# Sheet1.net
KiCad netlist of a schematic drawn in Altium Designer
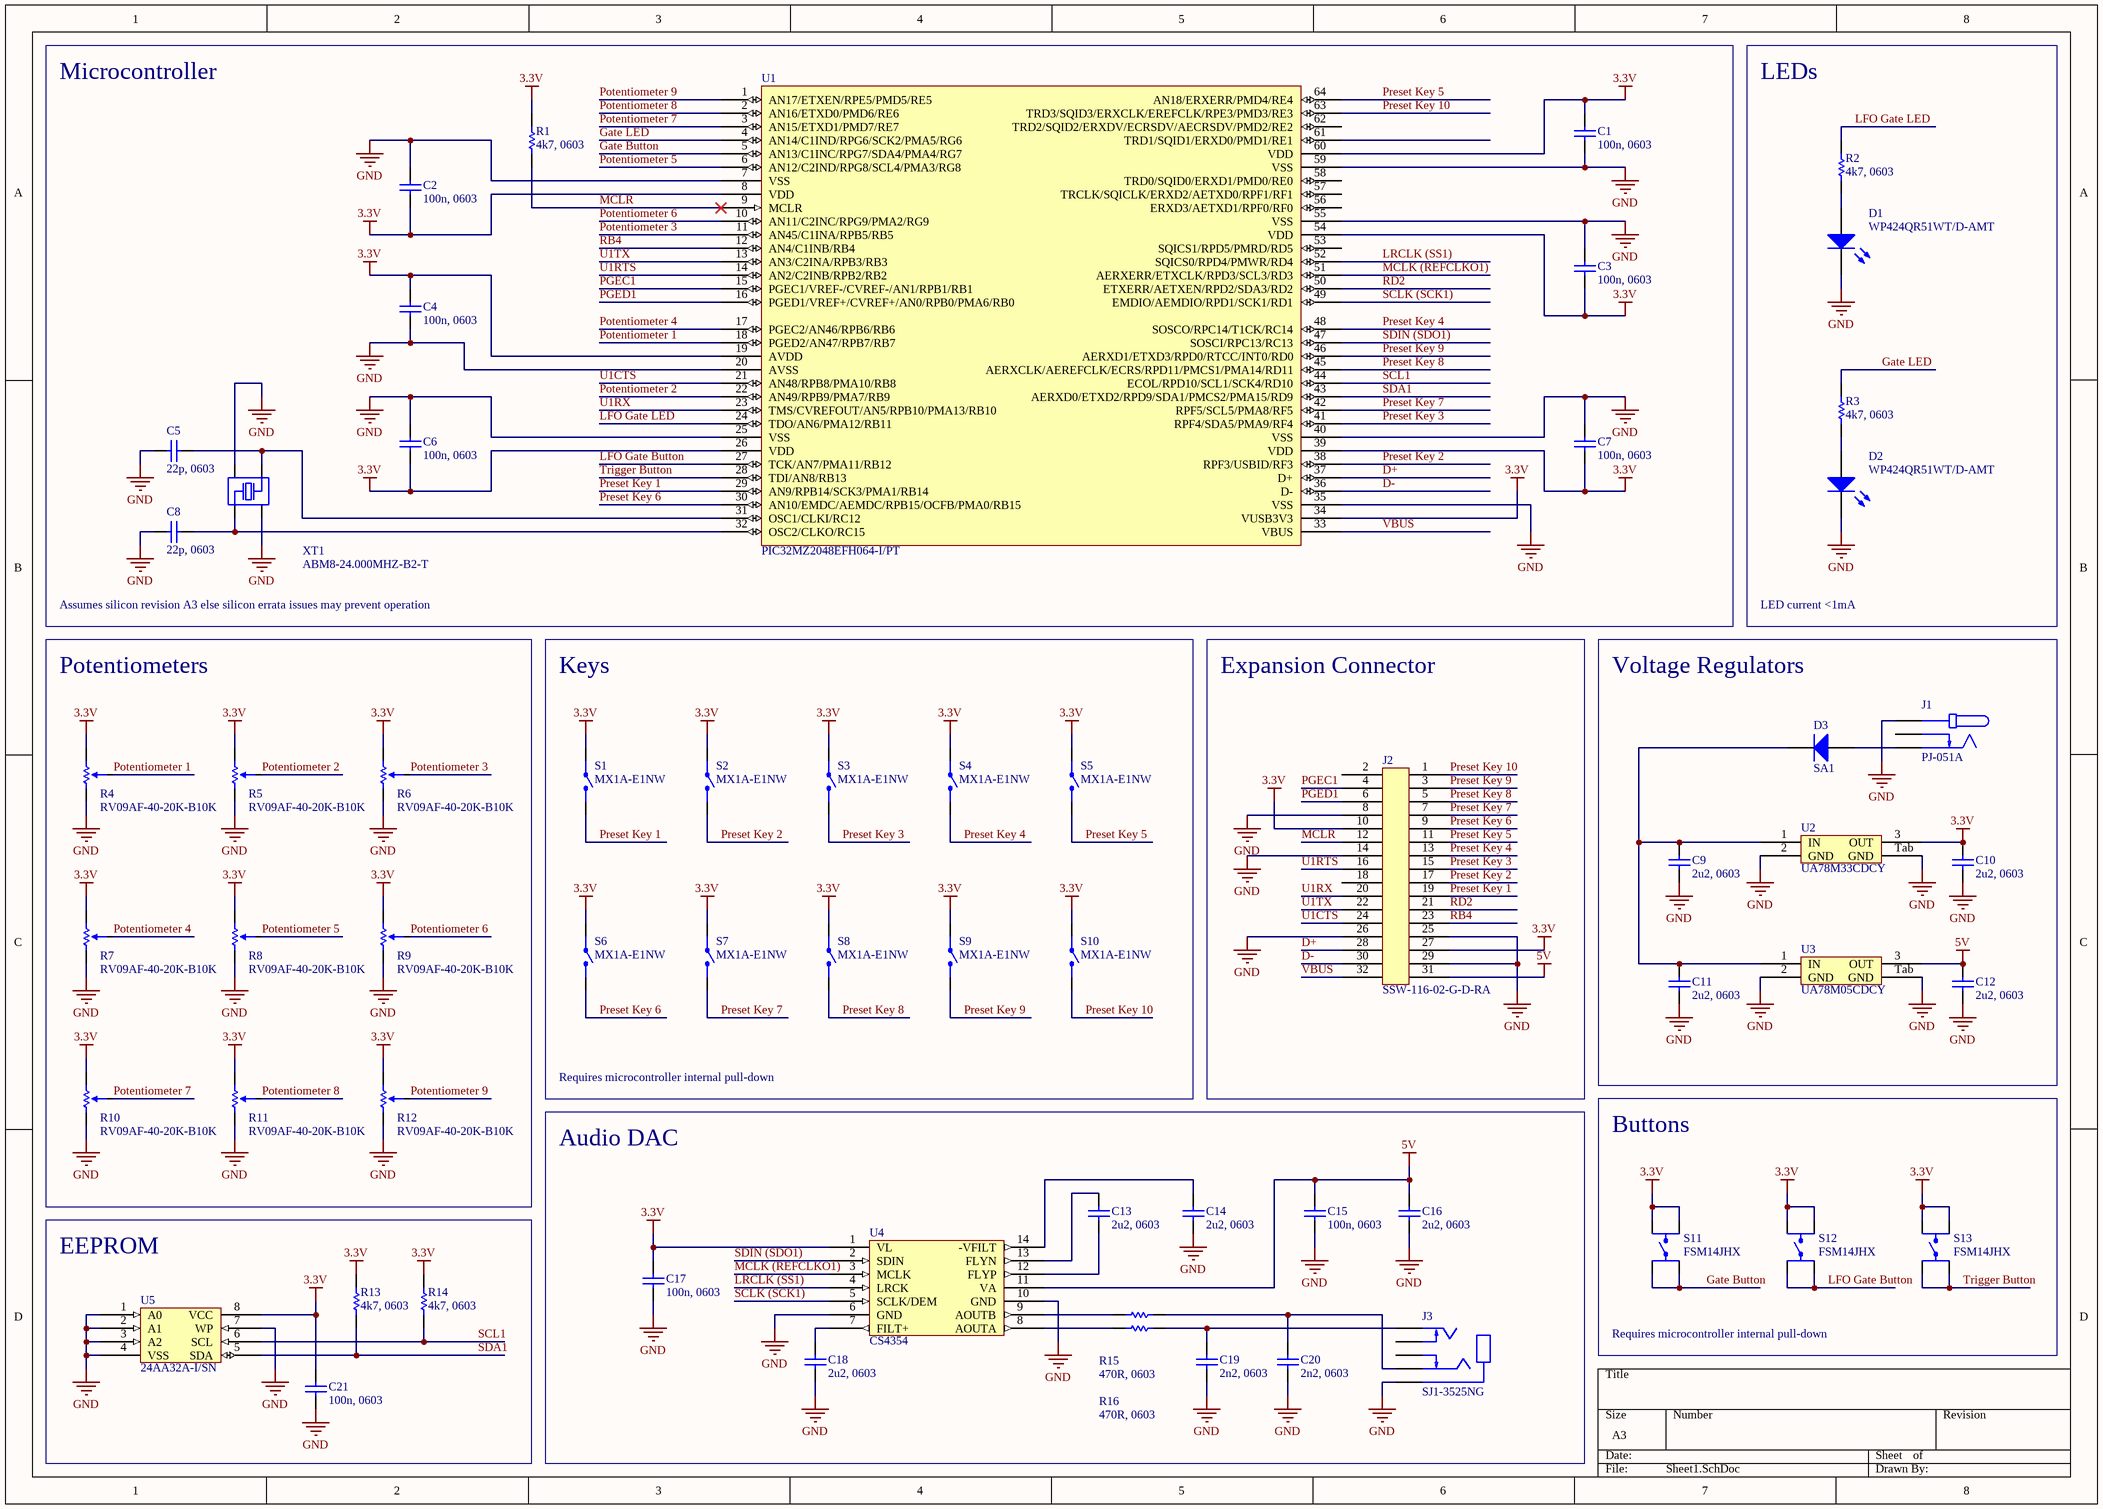
[diagram p0: Sheet1.SchDoc]

(export (version "E")
  (design (tool "Eeschema 10.0.6"))
  (components
    (comp (ref "C1")
      (value "100n, 0603")
      (footprint "Capacitor 0603")
      (libsource (lib "x-io") (part "Capacitor"))
    )
    (comp (ref "C2")
      (value "100n, 0603")
      (footprint "Capacitor 0603")
      (libsource (lib "x-io") (part "Capacitor"))
    )
    (comp (ref "C3")
      (value "100n, 0603")
      (footprint "Capacitor 0603")
      (libsource (lib "x-io") (part "Capacitor"))
    )
    (comp (ref "C4")
      (value "100n, 0603")
      (footprint "Capacitor 0603")
      (libsource (lib "x-io") (part "Capacitor"))
    )
    (comp (ref "C5")
      (value "22p, 0603")
      (footprint "Capacitor 0603")
      (libsource (lib "x-io") (part "Capacitor"))
    )
    (comp (ref "C6")
      (value "100n, 0603")
      (footprint "Capacitor 0603")
      (libsource (lib "x-io") (part "Capacitor"))
    )
    (comp (ref "C7")
      (value "100n, 0603")
      (footprint "Capacitor 0603")
      (libsource (lib "x-io") (part "Capacitor"))
    )
    (comp (ref "C8")
      (value "22p, 0603")
      (footprint "Capacitor 0603")
      (libsource (lib "x-io") (part "Capacitor"))
    )
    (comp (ref "C9")
      (value "2u2, 0603")
      (footprint "Capacitor 0603")
      (libsource (lib "x-io") (part "Capacitor"))
    )
    (comp (ref "C10")
      (value "2u2, 0603")
      (footprint "Capacitor 0603")
      (libsource (lib "x-io") (part "Capacitor"))
    )
    (comp (ref "C11")
      (value "2u2, 0603")
      (footprint "Capacitor 0603")
      (libsource (lib "x-io") (part "Capacitor"))
    )
    (comp (ref "C12")
      (value "2u2, 0603")
      (footprint "Capacitor 0603")
      (libsource (lib "x-io") (part "Capacitor"))
    )
    (comp (ref "C13")
      (value "2u2, 0603")
      (footprint "Capacitor 0603")
      (libsource (lib "x-io") (part "Capacitor"))
    )
    (comp (ref "C14")
      (value "2u2, 0603")
      (footprint "Capacitor 0603")
      (libsource (lib "x-io") (part "Capacitor"))
    )
    (comp (ref "C15")
      (value "100n, 0603")
      (footprint "Capacitor 0603")
      (libsource (lib "x-io") (part "Capacitor"))
    )
    (comp (ref "C16")
      (value "2u2, 0603")
      (footprint "Capacitor 0603")
      (libsource (lib "x-io") (part "Capacitor"))
    )
    (comp (ref "C17")
      (value "100n, 0603")
      (footprint "Capacitor 0603")
      (libsource (lib "x-io") (part "Capacitor"))
    )
    (comp (ref "C18")
      (value "2u2, 0603")
      (footprint "Capacitor 0603")
      (libsource (lib "x-io") (part "Capacitor"))
    )
    (comp (ref "C19")
      (value "2n2, 0603")
      (footprint "Capacitor 0603")
      (libsource (lib "x-io") (part "Capacitor"))
    )
    (comp (ref "C20")
      (value "2n2, 0603")
      (footprint "Capacitor 0603")
      (libsource (lib "x-io") (part "Capacitor"))
    )
    (comp (ref "C21")
      (value "100n, 0603")
      (footprint "Capacitor 0603")
      (libsource (lib "x-io") (part "Capacitor"))
    )
    (comp (ref "D1") (value "WP424QR51WT/D-AMT") (footprint "LED 3mm") (libsource (lib "x-io") (part "LED")))
    (comp (ref "D2") (value "WP424QR51WT/D-AMT") (footprint "LED 3mm") (libsource (lib "x-io") (part "LED")))
    (comp (ref "D3") (value "SA1") (footprint "DO-214AC") (libsource (lib "x-io") (part "Diode")))
    (comp (ref "J1") (value "PJ-051A") (footprint "PJ-051A") (libsource (lib "x-io") (part "PJ-051A")))
    (comp (ref "J2")
      (value "SSW-116-02-G-D-RA")
      (footprint "SSW-116-02-G-D-RA")
      (libsource (lib "x-io") (part "SSW-116-02-G-D-RA"))
    )
    (comp (ref "J3")
      (value "SJ1-3525NG")
      (footprint "SJ1-3525NG")
      (libsource (lib "x-io") (part "SJ1-3525NG"))
    )
    (comp (ref "R1")
      (value "4k7, 0603")
      (footprint "Resistor 0603")
      (libsource (lib "x-io") (part "Resistor"))
    )
    (comp (ref "R2")
      (value "4k7, 0603")
      (footprint "Resistor 0603")
      (libsource (lib "x-io") (part "Resistor"))
    )
    (comp (ref "R3")
      (value "4k7, 0603")
      (footprint "Resistor 0603")
      (libsource (lib "x-io") (part "Resistor"))
    )
    (comp (ref "R4")
      (value "RV09AF-40-20K-B10K")
      (footprint "RV09ACF-40")
      (libsource (lib "x-io") (part "Potentiometer"))
    )
    (comp (ref "R5")
      (value "RV09AF-40-20K-B10K")
      (footprint "RV09ACF-40")
      (libsource (lib "x-io") (part "Potentiometer"))
    )
    (comp (ref "R6")
      (value "RV09AF-40-20K-B10K")
      (footprint "RV09ACF-40")
      (libsource (lib "x-io") (part "Potentiometer"))
    )
    (comp (ref "R7")
      (value "RV09AF-40-20K-B10K")
      (footprint "RV09ACF-40")
      (libsource (lib "x-io") (part "Potentiometer"))
    )
    (comp (ref "R8")
      (value "RV09AF-40-20K-B10K")
      (footprint "RV09ACF-40")
      (libsource (lib "x-io") (part "Potentiometer"))
    )
    (comp (ref "R9")
      (value "RV09AF-40-20K-B10K")
      (footprint "RV09ACF-40")
      (libsource (lib "x-io") (part "Potentiometer"))
    )
    (comp (ref "R10")
      (value "RV09AF-40-20K-B10K")
      (footprint "RV09ACF-40")
      (libsource (lib "x-io") (part "Potentiometer"))
    )
    (comp (ref "R11")
      (value "RV09AF-40-20K-B10K")
      (footprint "RV09ACF-40")
      (libsource (lib "x-io") (part "Potentiometer"))
    )
    (comp (ref "R12")
      (value "RV09AF-40-20K-B10K")
      (footprint "RV09ACF-40")
      (libsource (lib "x-io") (part "Potentiometer"))
    )
    (comp (ref "R13")
      (value "4k7, 0603")
      (footprint "Resistor 0603")
      (libsource (lib "x-io") (part "Resistor"))
    )
    (comp (ref "R14")
      (value "4k7, 0603")
      (footprint "Resistor 0603")
      (libsource (lib "x-io") (part "Resistor"))
    )
    (comp (ref "R15")
      (value "470R, 0603")
      (footprint "Resistor 0603")
      (libsource (lib "x-io") (part "Resistor"))
    )
    (comp (ref "R16")
      (value "470R, 0603")
      (footprint "Resistor 0603")
      (libsource (lib "x-io") (part "Resistor"))
    )
    (comp (ref "S1") (value "MX1A-E1NW") (footprint "MX1A") (libsource (lib "x-io") (part "MX1A")))
    (comp (ref "S2") (value "MX1A-E1NW") (footprint "MX1A") (libsource (lib "x-io") (part "MX1A")))
    (comp (ref "S3") (value "MX1A-E1NW") (footprint "MX1A") (libsource (lib "x-io") (part "MX1A")))
    (comp (ref "S4") (value "MX1A-E1NW") (footprint "MX1A") (libsource (lib "x-io") (part "MX1A")))
    (comp (ref "S5") (value "MX1A-E1NW") (footprint "MX1A") (libsource (lib "x-io") (part "MX1A")))
    (comp (ref "S6") (value "MX1A-E1NW") (footprint "MX1A") (libsource (lib "x-io") (part "MX1A")))
    (comp (ref "S7") (value "MX1A-E1NW") (footprint "MX1A") (libsource (lib "x-io") (part "MX1A")))
    (comp (ref "S8") (value "MX1A-E1NW") (footprint "MX1A") (libsource (lib "x-io") (part "MX1A")))
    (comp (ref "S9") (value "MX1A-E1NW") (footprint "MX1A") (libsource (lib "x-io") (part "MX1A")))
    (comp (ref "S10") (value "MX1A-E1NW") (footprint "MX1A") (libsource (lib "x-io") (part "MX1A")))
    (comp (ref "S11")
      (value "FSM14JHX")
      (footprint "FSM14JHX")
      (libsource (lib "x-io") (part "Tactile Switch"))
    )
    (comp (ref "S12")
      (value "FSM14JHX")
      (footprint "FSM14JHX")
      (libsource (lib "x-io") (part "Tactile Switch"))
    )
    (comp (ref "S13")
      (value "FSM14JHX")
      (footprint "FSM14JHX")
      (libsource (lib "x-io") (part "Tactile Switch"))
    )
    (comp (ref "U1")
      (value "PIC32MZ2048EFH064-I/PT")
      (footprint "TQFP64")
      (libsource (lib "x-io") (part "PIC32MZ2048EFH064-I/PT"))
    )
    (comp (ref "U2") (value "UA78M33CDCY") (footprint "SOT-223") (libsource (lib "x-io") (part "µA78Mxx")))
    (comp (ref "U3") (value "UA78M05CDCY") (footprint "SOT-223") (libsource (lib "x-io") (part "µA78Mxx")))
    (comp (ref "U4") (value "CS4354") (footprint "SOIC14") (libsource (lib "x-io") (part "CS4354")))
    (comp (ref "U5") (value "24AA32A-I/SN") (footprint "SOIC8") (libsource (lib "x-io") (part "24AAxx")))
    (comp (ref "XT1")
      (value "ABM8-24.000MHZ-B2-T")
      (footprint "ABM8")
      (libsource (lib "x-io") (part "ABM8-16.000MHz-B2-T"))
    )
  )
  (nets
    (net (code "1") (name "/D+") (class "Default")
      (node (ref "J2") (pin "28") (pinfunction "*_28") (pintype "passive"))
      (node (ref "U1") (pin "37") (pinfunction "D+_37") (pintype "bidirectional"))
    )
    (net (code "2") (name "/D-") (class "Default")
      (node (ref "J2") (pin "30") (pinfunction "*_30") (pintype "passive"))
      (node (ref "U1") (pin "36") (pinfunction "D-_36") (pintype "bidirectional"))
    )
    (net (code "3") (name "/Gate Button") (class "Default")
      (node (ref "S11") (pin "1") (pinfunction "1_1") (pintype "passive"))
      (node (ref "S11") (pin "2") (pinfunction "2_2") (pintype "passive"))
      (node (ref "U1") (pin "5") (pinfunction "AN13/C1INC/RPG7/SDA4/PMA4/RG7_5") (pintype "bidirectional"))
    )
    (net (code "4") (name "/Gate LED") (class "Default")
      (node (ref "R3") (pin "2") (pinfunction "2_2") (pintype "passive"))
      (node (ref "U1") (pin "4") (pinfunction "AN14/C1IND/RPG6/SCK2/PMA5/RG6_4") (pintype "bidirectional"))
    )
    (net (code "5") (name "/LFO Gate Button") (class "Default")
      (node (ref "S12") (pin "1") (pinfunction "1_1") (pintype "passive"))
      (node (ref "S12") (pin "2") (pinfunction "2_2") (pintype "passive"))
      (node (ref "U1") (pin "27") (pinfunction "TCK/AN7/PMA11/RB12_27") (pintype "bidirectional"))
    )
    (net (code "6") (name "/LFO Gate LED") (class "Default")
      (node (ref "R2") (pin "2") (pinfunction "2_2") (pintype "passive"))
      (node (ref "U1") (pin "24") (pinfunction "TDO/AN6/PMA12/RB11_24") (pintype "bidirectional"))
    )
    (net (code "7") (name "/LRCLK (SS1)") (class "Default")
      (node (ref "U1") (pin "52") (pinfunction "SQICS0/RPD4/PMWR/RD4_52") (pintype "bidirectional"))
      (node (ref "U4") (pin "4") (pinfunction "LRCK_4") (pintype "input"))
    )
    (net (code "8") (name "/MCLK (REFCLKO1)") (class "Default")
      (node (ref "U1") (pin "51") (pinfunction "AERXERR/ETXCLK/RPD3/SCL3/RD3_51") (pintype "bidirectional"))
      (node (ref "U4") (pin "3") (pinfunction "MCLK_3") (pintype "input"))
    )
    (net (code "9") (name "/MCLR") (class "Default")
      (node (ref "J2") (pin "12") (pinfunction "*_12") (pintype "passive"))
      (node (ref "R1") (pin "1") (pinfunction "1_1") (pintype "passive"))
      (node (ref "U1") (pin "9") (pinfunction "MCLR_9") (pintype "input"))
    )
    (net (code "10") (name "/PGEC1") (class "Default")
      (node (ref "J2") (pin "4") (pinfunction "*_4") (pintype "passive"))
      (node (ref "U1") (pin "15") (pinfunction "PGEC1/VREF-/CVREF-/AN1/RPB1/RB1_15") (pintype "bidirectional"))
    )
    (net (code "11") (name "/PGED1") (class "Default")
      (node (ref "J2") (pin "6") (pinfunction "*_6") (pintype "passive"))
      (node (ref "U1") (pin "16") (pinfunction "PGED1/VREF+/CVREF+/AN0/RPB0/PMA6/RB0_16") (pintype "bidirectional"))
    )
    (net (code "12") (name "/Potentiometer 1") (class "Default")
      (node (ref "R4") (pin "2") (pinfunction "2_2") (pintype "passive"))
      (node (ref "U1") (pin "18") (pinfunction "PGED2/AN47/RPB7/RB7_18") (pintype "bidirectional"))
    )
    (net (code "13") (name "/Potentiometer 2") (class "Default")
      (node (ref "R5") (pin "2") (pinfunction "2_2") (pintype "passive"))
      (node (ref "U1") (pin "22") (pinfunction "AN49/RPB9/PMA7/RB9_22") (pintype "bidirectional"))
    )
    (net (code "14") (name "/Potentiometer 3") (class "Default")
      (node (ref "R6") (pin "2") (pinfunction "2_2") (pintype "passive"))
      (node (ref "U1") (pin "11") (pinfunction "AN45/C1INA/RPB5/RB5_11") (pintype "bidirectional"))
    )
    (net (code "15") (name "/Potentiometer 4") (class "Default")
      (node (ref "R7") (pin "2") (pinfunction "2_2") (pintype "passive"))
      (node (ref "U1") (pin "17") (pinfunction "PGEC2/AN46/RPB6/RB6_17") (pintype "bidirectional"))
    )
    (net (code "16") (name "/Potentiometer 5") (class "Default")
      (node (ref "R8") (pin "2") (pinfunction "2_2") (pintype "passive"))
      (node (ref "U1") (pin "6") (pinfunction "AN12/C2IND/RPG8/SCL4/PMA3/RG8_6") (pintype "bidirectional"))
    )
    (net (code "17") (name "/Potentiometer 6") (class "Default")
      (node (ref "R9") (pin "2") (pinfunction "2_2") (pintype "passive"))
      (node (ref "U1") (pin "10") (pinfunction "AN11/C2INC/RPG9/PMA2/RG9_10") (pintype "bidirectional"))
    )
    (net (code "18") (name "/Potentiometer 7") (class "Default")
      (node (ref "R10") (pin "2") (pinfunction "2_2") (pintype "passive"))
      (node (ref "U1") (pin "3") (pinfunction "AN15/ETXD1/PMD7/RE7_3") (pintype "bidirectional"))
    )
    (net (code "19") (name "/Potentiometer 8") (class "Default")
      (node (ref "R11") (pin "2") (pinfunction "2_2") (pintype "passive"))
      (node (ref "U1") (pin "2") (pinfunction "AN16/ETXD0/PMD6/RE6_2") (pintype "bidirectional"))
    )
    (net (code "20") (name "/Potentiometer 9") (class "Default")
      (node (ref "R12") (pin "2") (pinfunction "2_2") (pintype "passive"))
      (node (ref "U1") (pin "1") (pinfunction "AN17/ETXEN/RPE5/PMD5/RE5_1") (pintype "bidirectional"))
    )
    (net (code "21") (name "/Preset Key 1") (class "Default")
      (node (ref "J2") (pin "19") (pinfunction "*_19") (pintype "passive"))
      (node (ref "S1") (pin "2") (pinfunction "2_2") (pintype "passive"))
      (node (ref "U1") (pin "29") (pinfunction "AN9/RPB14/SCK3/PMA1/RB14_29") (pintype "bidirectional"))
    )
    (net (code "22") (name "/Preset Key 2") (class "Default")
      (node (ref "J2") (pin "17") (pinfunction "*_17") (pintype "passive"))
      (node (ref "S2") (pin "2") (pinfunction "2_2") (pintype "passive"))
      (node (ref "U1") (pin "38") (pinfunction "RPF3/USBID/RF3_38") (pintype "bidirectional"))
    )
    (net (code "23") (name "/Preset Key 3") (class "Default")
      (node (ref "J2") (pin "15") (pinfunction "*_15") (pintype "passive"))
      (node (ref "S3") (pin "2") (pinfunction "2_2") (pintype "passive"))
      (node (ref "U1") (pin "41") (pinfunction "RPF4/SDA5/PMA9/RF4_41") (pintype "bidirectional"))
    )
    (net (code "24") (name "/Preset Key 4") (class "Default")
      (node (ref "J2") (pin "13") (pinfunction "*_13") (pintype "passive"))
      (node (ref "S4") (pin "2") (pinfunction "2_2") (pintype "passive"))
      (node (ref "U1") (pin "48") (pinfunction "SOSCO/RPC14/T1CK/RC14_48") (pintype "bidirectional"))
    )
    (net (code "25") (name "/Preset Key 5") (class "Default")
      (node (ref "J2") (pin "11") (pinfunction "*_11") (pintype "passive"))
      (node (ref "S5") (pin "2") (pinfunction "2_2") (pintype "passive"))
      (node (ref "U1") (pin "64") (pinfunction "AN18/ERXERR/PMD4/RE4_64") (pintype "bidirectional"))
    )
    (net (code "26") (name "/Preset Key 6") (class "Default")
      (node (ref "J2") (pin "9") (pinfunction "*_9") (pintype "passive"))
      (node (ref "S6") (pin "2") (pinfunction "2_2") (pintype "passive"))
      (node (ref "U1") (pin "30") (pinfunction "AN10/EMDC/AEMDC/RPB15/OCFB/PMA0/RB15_30") (pintype "bidirectional"))
    )
    (net (code "27") (name "/Preset Key 7") (class "Default")
      (node (ref "J2") (pin "7") (pinfunction "*_7") (pintype "passive"))
      (node (ref "S7") (pin "2") (pinfunction "2_2") (pintype "passive"))
      (node (ref "U1") (pin "42") (pinfunction "RPF5/SCL5/PMA8/RF5_42") (pintype "bidirectional"))
    )
    (net (code "28") (name "/Preset Key 8") (class "Default")
      (node (ref "J2") (pin "5") (pinfunction "*_5") (pintype "passive"))
      (node (ref "S8") (pin "2") (pinfunction "2_2") (pintype "passive"))
      (node (ref "U1") (pin "45") (pinfunction "AERXCLK/AEREFCLK/ECRS/RPD11/PMCS1/PMA14/RD11_45") (pintype "bidirectional"))
    )
    (net (code "29") (name "/Preset Key 9") (class "Default")
      (node (ref "J2") (pin "3") (pinfunction "*_3") (pintype "passive"))
      (node (ref "S9") (pin "2") (pinfunction "2_2") (pintype "passive"))
      (node (ref "U1") (pin "46") (pinfunction "AERXD1/ETXD3/RPD0/RTCC/INT0/RD0_46") (pintype "bidirectional"))
    )
    (net (code "30") (name "/Preset Key 10") (class "Default")
      (node (ref "J2") (pin "1") (pinfunction "*_1") (pintype "passive"))
      (node (ref "S10") (pin "2") (pinfunction "2_2") (pintype "passive"))
      (node (ref "U1") (pin "63") (pinfunction "TRD3/SQID3/ERXCLK/EREFCLK/RPE3/PMD3/RE3_63") (pintype "bidirectional"))
    )
    (net (code "31") (name "/RB4") (class "Default")
      (node (ref "J2") (pin "23") (pinfunction "*_23") (pintype "passive"))
      (node (ref "U1") (pin "12") (pinfunction "AN4/C1INB/RB4_12") (pintype "bidirectional"))
    )
    (net (code "32") (name "/RD2") (class "Default")
      (node (ref "J2") (pin "21") (pinfunction "*_21") (pintype "passive"))
      (node (ref "U1") (pin "50") (pinfunction "ETXERR/AETXEN/RPD2/SDA3/RD2_50") (pintype "bidirectional"))
    )
    (net (code "33") (name "/SCL1") (class "Default")
      (node (ref "R14") (pin "1") (pinfunction "1_1") (pintype "passive"))
      (node (ref "U1") (pin "44") (pinfunction "ECOL/RPD10/SCL1/SCK4/RD10_44") (pintype "bidirectional"))
      (node (ref "U5") (pin "6") (pinfunction "SCL_6") (pintype "input"))
    )
    (net (code "34") (name "/SCLK (SCK1)") (class "Default")
      (node (ref "U1") (pin "49") (pinfunction "EMDIO/AEMDIO/RPD1/SCK1/RD1_49") (pintype "bidirectional"))
      (node (ref "U4") (pin "5") (pinfunction "SCLK/DEM_5") (pintype "input"))
    )
    (net (code "35") (name "/SDA1") (class "Default")
      (node (ref "R13") (pin "1") (pinfunction "1_1") (pintype "passive"))
      (node (ref "U1") (pin "43") (pinfunction "AERXD0/ETXD2/RPD9/SDA1/PMCS2/PMA15/RD9_43") (pintype "bidirectional"))
      (node (ref "U5") (pin "5") (pinfunction "SDA_5") (pintype "bidirectional"))
    )
    (net (code "36") (name "/SDIN (SDO1)") (class "Default")
      (node (ref "U1") (pin "47") (pinfunction "SOSCI/RPC13/RC13_47") (pintype "bidirectional"))
      (node (ref "U4") (pin "2") (pinfunction "SDIN_2") (pintype "input"))
    )
    (net (code "37") (name "/Trigger Button") (class "Default")
      (node (ref "S13") (pin "1") (pinfunction "1_1") (pintype "passive"))
      (node (ref "S13") (pin "2") (pinfunction "2_2") (pintype "passive"))
      (node (ref "U1") (pin "28") (pinfunction "TDI/AN8/RB13_28") (pintype "bidirectional"))
    )
    (net (code "38") (name "/U1CTS") (class "Default")
      (node (ref "J2") (pin "24") (pinfunction "*_24") (pintype "passive"))
      (node (ref "U1") (pin "21") (pinfunction "AN48/RPB8/PMA10/RB8_21") (pintype "bidirectional"))
    )
    (net (code "39") (name "/U1RTS") (class "Default")
      (node (ref "J2") (pin "16") (pinfunction "*_16") (pintype "passive"))
      (node (ref "U1") (pin "14") (pinfunction "AN2/C2INB/RPB2/RB2_14") (pintype "bidirectional"))
    )
    (net (code "40") (name "/U1RX") (class "Default")
      (node (ref "J2") (pin "20") (pinfunction "*_20") (pintype "passive"))
      (node (ref "U1") (pin "23") (pinfunction "TMS/CVREFOUT/AN5/RPB10/PMA13/RB10_23") (pintype "bidirectional"))
    )
    (net (code "41") (name "/U1TX") (class "Default")
      (node (ref "J2") (pin "22") (pinfunction "*_22") (pintype "passive"))
      (node (ref "U1") (pin "13") (pinfunction "AN3/C2INA/RPB3/RB3_13") (pintype "bidirectional"))
    )
    (net (code "42") (name "/VBUS") (class "Default")
      (node (ref "J2") (pin "32") (pinfunction "*_32") (pintype "passive"))
      (node (ref "U1") (pin "33") (pinfunction "VBUS_33") (pintype "power_in"))
    )
    (net (code "43") (name "3.3V") (class "Default")
      (node (ref "C1") (pin "1") (pinfunction "1_1") (pintype "passive"))
      (node (ref "C10") (pin "2") (pinfunction "2_2") (pintype "passive"))
      (node (ref "C17") (pin "2") (pinfunction "2_2") (pintype "passive"))
      (node (ref "C2") (pin "1") (pinfunction "1_1") (pintype "passive"))
      (node (ref "C21") (pin "2") (pinfunction "2_2") (pintype "passive"))
      (node (ref "C3") (pin "2") (pinfunction "2_2") (pintype "passive"))
      (node (ref "C4") (pin "2") (pinfunction "2_2") (pintype "passive"))
      (node (ref "C6") (pin "1") (pinfunction "1_1") (pintype "passive"))
      (node (ref "C7") (pin "2") (pinfunction "2_2") (pintype "passive"))
      (node (ref "J2") (pin "10") (pinfunction "*_10") (pintype "passive"))
      (node (ref "J2") (pin "27") (pinfunction "*_27") (pintype "passive"))
      (node (ref "R1") (pin "2") (pinfunction "2_2") (pintype "passive"))
      (node (ref "R10") (pin "3") (pinfunction "3_3") (pintype "passive"))
      (node (ref "R11") (pin "3") (pinfunction "3_3") (pintype "passive"))
      (node (ref "R12") (pin "3") (pinfunction "3_3") (pintype "passive"))
      (node (ref "R13") (pin "2") (pinfunction "2_2") (pintype "passive"))
      (node (ref "R14") (pin "2") (pinfunction "2_2") (pintype "passive"))
      (node (ref "R4") (pin "3") (pinfunction "3_3") (pintype "passive"))
      (node (ref "R5") (pin "3") (pinfunction "3_3") (pintype "passive"))
      (node (ref "R6") (pin "3") (pinfunction "3_3") (pintype "passive"))
      (node (ref "R7") (pin "3") (pinfunction "3_3") (pintype "passive"))
      (node (ref "R8") (pin "3") (pinfunction "3_3") (pintype "passive"))
      (node (ref "R9") (pin "3") (pinfunction "3_3") (pintype "passive"))
      (node (ref "S1") (pin "1") (pinfunction "1_1") (pintype "passive"))
      (node (ref "S10") (pin "1") (pinfunction "1_1") (pintype "passive"))
      (node (ref "S11") (pin "3") (pinfunction "3_3") (pintype "passive"))
      (node (ref "S11") (pin "4") (pinfunction "4_4") (pintype "passive"))
      (node (ref "S12") (pin "3") (pinfunction "3_3") (pintype "passive"))
      (node (ref "S12") (pin "4") (pinfunction "4_4") (pintype "passive"))
      (node (ref "S13") (pin "3") (pinfunction "3_3") (pintype "passive"))
      (node (ref "S13") (pin "4") (pinfunction "4_4") (pintype "passive"))
      (node (ref "S2") (pin "1") (pinfunction "1_1") (pintype "passive"))
      (node (ref "S3") (pin "1") (pinfunction "1_1") (pintype "passive"))
      (node (ref "S4") (pin "1") (pinfunction "1_1") (pintype "passive"))
      (node (ref "S5") (pin "1") (pinfunction "1_1") (pintype "passive"))
      (node (ref "S6") (pin "1") (pinfunction "1_1") (pintype "passive"))
      (node (ref "S7") (pin "1") (pinfunction "1_1") (pintype "passive"))
      (node (ref "S8") (pin "1") (pinfunction "1_1") (pintype "passive"))
      (node (ref "S9") (pin "1") (pinfunction "1_1") (pintype "passive"))
      (node (ref "U1") (pin "19") (pinfunction "AVDD_19") (pintype "power_in"))
      (node (ref "U1") (pin "26") (pinfunction "VDD_26") (pintype "power_in"))
      (node (ref "U1") (pin "34") (pinfunction "VUSB3V3_34") (pintype "power_in"))
      (node (ref "U1") (pin "39") (pinfunction "VDD_39") (pintype "power_in"))
      (node (ref "U1") (pin "54") (pinfunction "VDD_54") (pintype "power_in"))
      (node (ref "U1") (pin "60") (pinfunction "VDD_60") (pintype "power_in"))
      (node (ref "U1") (pin "8") (pinfunction "VDD_8") (pintype "power_in"))
      (node (ref "U2") (pin "3") (pinfunction "OUT_3") (pintype "power_in"))
      (node (ref "U4") (pin "1") (pinfunction "VL_1") (pintype "power_in"))
      (node (ref "U5") (pin "8") (pinfunction "VCC_8") (pintype "power_in"))
    )
    (net (code "44") (name "5V") (class "Default")
      (node (ref "C12") (pin "2") (pinfunction "2_2") (pintype "passive"))
      (node (ref "C15") (pin "2") (pinfunction "2_2") (pintype "passive"))
      (node (ref "C16") (pin "2") (pinfunction "2_2") (pintype "passive"))
      (node (ref "J2") (pin "31") (pinfunction "*_31") (pintype "passive"))
      (node (ref "U3") (pin "3") (pinfunction "OUT_3") (pintype "power_in"))
      (node (ref "U4") (pin "11") (pinfunction "VA_11") (pintype "power_in"))
    )
    (net (code "45") (name "GND") (class "Default")
      (node (ref "C1") (pin "2") (pinfunction "2_2") (pintype "passive"))
      (node (ref "C10") (pin "1") (pinfunction "1_1") (pintype "passive"))
      (node (ref "C11") (pin "1") (pinfunction "1_1") (pintype "passive"))
      (node (ref "C12") (pin "1") (pinfunction "1_1") (pintype "passive"))
      (node (ref "C14") (pin "1") (pinfunction "1_1") (pintype "passive"))
      (node (ref "C15") (pin "1") (pinfunction "1_1") (pintype "passive"))
      (node (ref "C16") (pin "1") (pinfunction "1_1") (pintype "passive"))
      (node (ref "C17") (pin "1") (pinfunction "1_1") (pintype "passive"))
      (node (ref "C18") (pin "1") (pinfunction "1_1") (pintype "passive"))
      (node (ref "C19") (pin "1") (pinfunction "1_1") (pintype "passive"))
      (node (ref "C2") (pin "2") (pinfunction "2_2") (pintype "passive"))
      (node (ref "C20") (pin "1") (pinfunction "1_1") (pintype "passive"))
      (node (ref "C21") (pin "1") (pinfunction "1_1") (pintype "passive"))
      (node (ref "C3") (pin "1") (pinfunction "1_1") (pintype "passive"))
      (node (ref "C4") (pin "1") (pinfunction "1_1") (pintype "passive"))
      (node (ref "C5") (pin "1") (pinfunction "1_1") (pintype "passive"))
      (node (ref "C6") (pin "2") (pinfunction "2_2") (pintype "passive"))
      (node (ref "C7") (pin "1") (pinfunction "1_1") (pintype "passive"))
      (node (ref "C8") (pin "1") (pinfunction "1_1") (pintype "passive"))
      (node (ref "C9") (pin "1") (pinfunction "1_1") (pintype "passive"))
      (node (ref "D1") (pin "K") (pinfunction "K_K") (pintype "passive"))
      (node (ref "D2") (pin "K") (pinfunction "K_K") (pintype "passive"))
      (node (ref "J1") (pin "1") (pinfunction "1_1") (pintype "passive"))
      (node (ref "J2") (pin "14") (pinfunction "*_14") (pintype "passive"))
      (node (ref "J2") (pin "25") (pinfunction "*_25") (pintype "passive"))
      (node (ref "J2") (pin "26") (pinfunction "*_26") (pintype "passive"))
      (node (ref "J2") (pin "29") (pinfunction "*_29") (pintype "passive"))
      (node (ref "J2") (pin "8") (pinfunction "*_8") (pintype "passive"))
      (node (ref "J3") (pin "1") (pinfunction "sleeve_1") (pintype "passive"))
      (node (ref "R10") (pin "1") (pinfunction "1_1") (pintype "passive"))
      (node (ref "R11") (pin "1") (pinfunction "1_1") (pintype "passive"))
      (node (ref "R12") (pin "1") (pinfunction "1_1") (pintype "passive"))
      (node (ref "R4") (pin "1") (pinfunction "1_1") (pintype "passive"))
      (node (ref "R5") (pin "1") (pinfunction "1_1") (pintype "passive"))
      (node (ref "R6") (pin "1") (pinfunction "1_1") (pintype "passive"))
      (node (ref "R7") (pin "1") (pinfunction "1_1") (pintype "passive"))
      (node (ref "R8") (pin "1") (pinfunction "1_1") (pintype "passive"))
      (node (ref "R9") (pin "1") (pinfunction "1_1") (pintype "passive"))
      (node (ref "U1") (pin "20") (pinfunction "AVSS_20") (pintype "power_in"))
      (node (ref "U1") (pin "25") (pinfunction "VSS_25") (pintype "power_in"))
      (node (ref "U1") (pin "35") (pinfunction "VSS_35") (pintype "power_in"))
      (node (ref "U1") (pin "40") (pinfunction "VSS_40") (pintype "power_in"))
      (node (ref "U1") (pin "55") (pinfunction "VSS_55") (pintype "power_in"))
      (node (ref "U1") (pin "59") (pinfunction "VSS_59") (pintype "power_in"))
      (node (ref "U1") (pin "7") (pinfunction "VSS_7") (pintype "power_in"))
      (node (ref "U2") (pin "2") (pinfunction "GND_2") (pintype "power_in"))
      (node (ref "U2") (pin "Tab") (pinfunction "GND_Tab") (pintype "power_in"))
      (node (ref "U3") (pin "2") (pinfunction "GND_2") (pintype "power_in"))
      (node (ref "U3") (pin "Tab") (pinfunction "GND_Tab") (pintype "power_in"))
      (node (ref "U4") (pin "10") (pinfunction "GND_10") (pintype "power_in"))
      (node (ref "U4") (pin "6") (pinfunction "GND_6") (pintype "power_in"))
      (node (ref "U5") (pin "1") (pinfunction "A0_1") (pintype "input"))
      (node (ref "U5") (pin "2") (pinfunction "A1_2") (pintype "input"))
      (node (ref "U5") (pin "3") (pinfunction "A2_3") (pintype "input"))
      (node (ref "U5") (pin "4") (pinfunction "VSS_4") (pintype "power_in"))
      (node (ref "U5") (pin "7") (pinfunction "WP_7") (pintype "input"))
      (node (ref "XT1") (pin "2") (pinfunction "GND_2") (pintype "passive"))
      (node (ref "XT1") (pin "4") (pinfunction "GND_4") (pintype "passive"))
    )
    (net (code "46") (name "Net-(D1-PadA)") (class "Default")
      (node (ref "D1") (pin "A") (pinfunction "A_A") (pintype "passive"))
      (node (ref "R2") (pin "1") (pinfunction "1_1") (pintype "passive"))
    )
    (net (code "47") (name "Net-(D2-PadA)") (class "Default")
      (node (ref "D2") (pin "A") (pinfunction "A_A") (pintype "passive"))
      (node (ref "R3") (pin "1") (pinfunction "1_1") (pintype "passive"))
    )
    (net (code "48") (name "Net-(D3-PadA)") (class "Default")
      (node (ref "D3") (pin "A") (pinfunction "A_A") (pintype "passive"))
      (node (ref "J1") (pin "2") (pinfunction "2_2") (pintype "passive"))
    )
    (net (code "49") (name "Net-(J3-ring)") (class "Default")
      (node (ref "C20") (pin "2") (pinfunction "2_2") (pintype "passive"))
      (node (ref "J3") (pin "3") (pinfunction "ring_3") (pintype "passive"))
      (node (ref "R15") (pin "2") (pinfunction "2_2") (pintype "passive"))
    )
    (net (code "50") (name "Net-(J3-tip)") (class "Default")
      (node (ref "C19") (pin "2") (pinfunction "2_2") (pintype "passive"))
      (node (ref "J3") (pin "2") (pinfunction "tip_2") (pintype "passive"))
      (node (ref "R16") (pin "2") (pinfunction "2_2") (pintype "passive"))
    )
    (net (code "51") (name "Net-(U1-OSC1{slash}CLKI{slash}RC12)") (class "Default")
      (node (ref "C5") (pin "2") (pinfunction "2_2") (pintype "passive"))
      (node (ref "U1") (pin "31") (pinfunction "OSC1/CLKI/RC12_31") (pintype "bidirectional"))
      (node (ref "XT1") (pin "1") (pinfunction "XT1_1") (pintype "passive"))
    )
    (net (code "52") (name "Net-(U1-OSC2{slash}CLKO{slash}RC15)") (class "Default")
      (node (ref "C8") (pin "2") (pinfunction "2_2") (pintype "passive"))
      (node (ref "U1") (pin "32") (pinfunction "OSC2/CLKO/RC15_32") (pintype "bidirectional"))
      (node (ref "XT1") (pin "3") (pinfunction "XT2_3") (pintype "passive"))
    )
    (net (code "53") (name "Net-(U2-IN)") (class "Default")
      (node (ref "C11") (pin "2") (pinfunction "2_2") (pintype "passive"))
      (node (ref "C9") (pin "2") (pinfunction "2_2") (pintype "passive"))
      (node (ref "D3") (pin "K") (pinfunction "K_K") (pintype "passive"))
      (node (ref "U2") (pin "1") (pinfunction "IN_1") (pintype "power_in"))
      (node (ref "U3") (pin "1") (pinfunction "IN_1") (pintype "power_in"))
    )
    (net (code "54") (name "Net-(U4--VFILT)") (class "Default")
      (node (ref "C14") (pin "2") (pinfunction "2_2") (pintype "passive"))
      (node (ref "U4") (pin "14") (pinfunction "-VFILT_14") (pintype "output"))
    )
    (net (code "55") (name "Net-(U4-AOUTA)") (class "Default")
      (node (ref "R16") (pin "1") (pinfunction "1_1") (pintype "passive"))
      (node (ref "U4") (pin "8") (pinfunction "AOUTA_8") (pintype "output"))
    )
    (net (code "56") (name "Net-(U4-AOUTB)") (class "Default")
      (node (ref "R15") (pin "1") (pinfunction "1_1") (pintype "passive"))
      (node (ref "U4") (pin "9") (pinfunction "AOUTB_9") (pintype "output"))
    )
    (net (code "57") (name "Net-(U4-FILT+)") (class "Default")
      (node (ref "C18") (pin "2") (pinfunction "2_2") (pintype "passive"))
      (node (ref "U4") (pin "7") (pinfunction "FILT+_7") (pintype "output"))
    )
    (net (code "58") (name "Net-(U4-FLYN)") (class "Default")
      (node (ref "C13") (pin "2") (pinfunction "2_2") (pintype "passive"))
      (node (ref "U4") (pin "13") (pinfunction "FLYN_13") (pintype "output"))
    )
    (net (code "59") (name "Net-(U4-FLYP)") (class "Default")
      (node (ref "C13") (pin "1") (pinfunction "1_1") (pintype "passive"))
      (node (ref "U4") (pin "12") (pinfunction "FLYP_12") (pintype "output"))
    )
    (net (code "60") (name "unconnected-(J1-Pad3)") (class "Default")
      (node (ref "J1") (pin "3") (pinfunction "3_3") (pintype "passive"))
    )
    (net (code "61") (name "unconnected-(J2-*-Pad2)") (class "Default")
      (node (ref "J2") (pin "2") (pinfunction "*_2") (pintype "passive"))
    )
    (net (code "62") (name "unconnected-(J2-*-Pad18)") (class "Default")
      (node (ref "J2") (pin "18") (pinfunction "*_18") (pintype "passive"))
    )
    (net (code "63") (name "unconnected-(J3-ring_switch-Pad5)") (class "Default")
      (node (ref "J3") (pin "5") (pinfunction "ring_switch_5") (pintype "passive"))
    )
    (net (code "64") (name "unconnected-(J3-tip_switch-Pad4)") (class "Default")
      (node (ref "J3") (pin "4") (pinfunction "tip_switch_4") (pintype "passive"))
    )
    (net (code "65") (name "unconnected-(U1-ERXD3{slash}AETXD1{slash}RPF0{slash}RF0-Pad56)") (class "Default")
      (node (ref "U1") (pin "56") (pinfunction "ERXD3/AETXD1/RPF0/RF0_56") (pintype "bidirectional"))
    )
    (net (code "66") (name "unconnected-(U1-SQICS1{slash}RPD5{slash}PMRD{slash}RD5-Pad53)") (class "Default")
      (node (ref "U1") (pin "53") (pinfunction "SQICS1/RPD5/PMRD/RD5_53") (pintype "bidirectional"))
    )
    (net (code "67") (name "unconnected-(U1-TRCLK{slash}SQICLK{slash}ERXD2{slash}AETXD0{slash}RPF1{slash}RF1-Pad57)") (class "Default")
      (node (ref "U1") (pin "57") (pinfunction "TRCLK/SQICLK/ERXD2/AETXD0/RPF1/RF1_57") (pintype "bidirectional"))
    )
    (net (code "68") (name "unconnected-(U1-TRD0{slash}SQID0{slash}ERXD1{slash}PMD0{slash}RE0-Pad58)") (class "Default")
      (node (ref "U1") (pin "58") (pinfunction "TRD0/SQID0/ERXD1/PMD0/RE0_58") (pintype "bidirectional"))
    )
    (net (code "69") (name "unconnected-(U1-TRD1{slash}SQID1{slash}ERXD0{slash}PMD1{slash}RE1-Pad61)") (class "Default")
      (node (ref "U1") (pin "61") (pinfunction "TRD1/SQID1/ERXD0/PMD1/RE1_61") (pintype "bidirectional"))
    )
    (net (code "70") (name "unconnected-(U1-TRD2{slash}SQID2{slash}ERXDV{slash}ECRSDV{slash}AECRSDV{slash}PMD2{slash}RE2-Pad62)") (class "Default")
      (node (ref "U1") (pin "62") (pinfunction "TRD2/SQID2/ERXDV/ECRSDV/AECRSDV/PMD2/RE2_62") (pintype "bidirectional"))
    )
  )
)
